# 6x3analogMUX.net
KiCad netlist of a schematic drawn in EAGLE
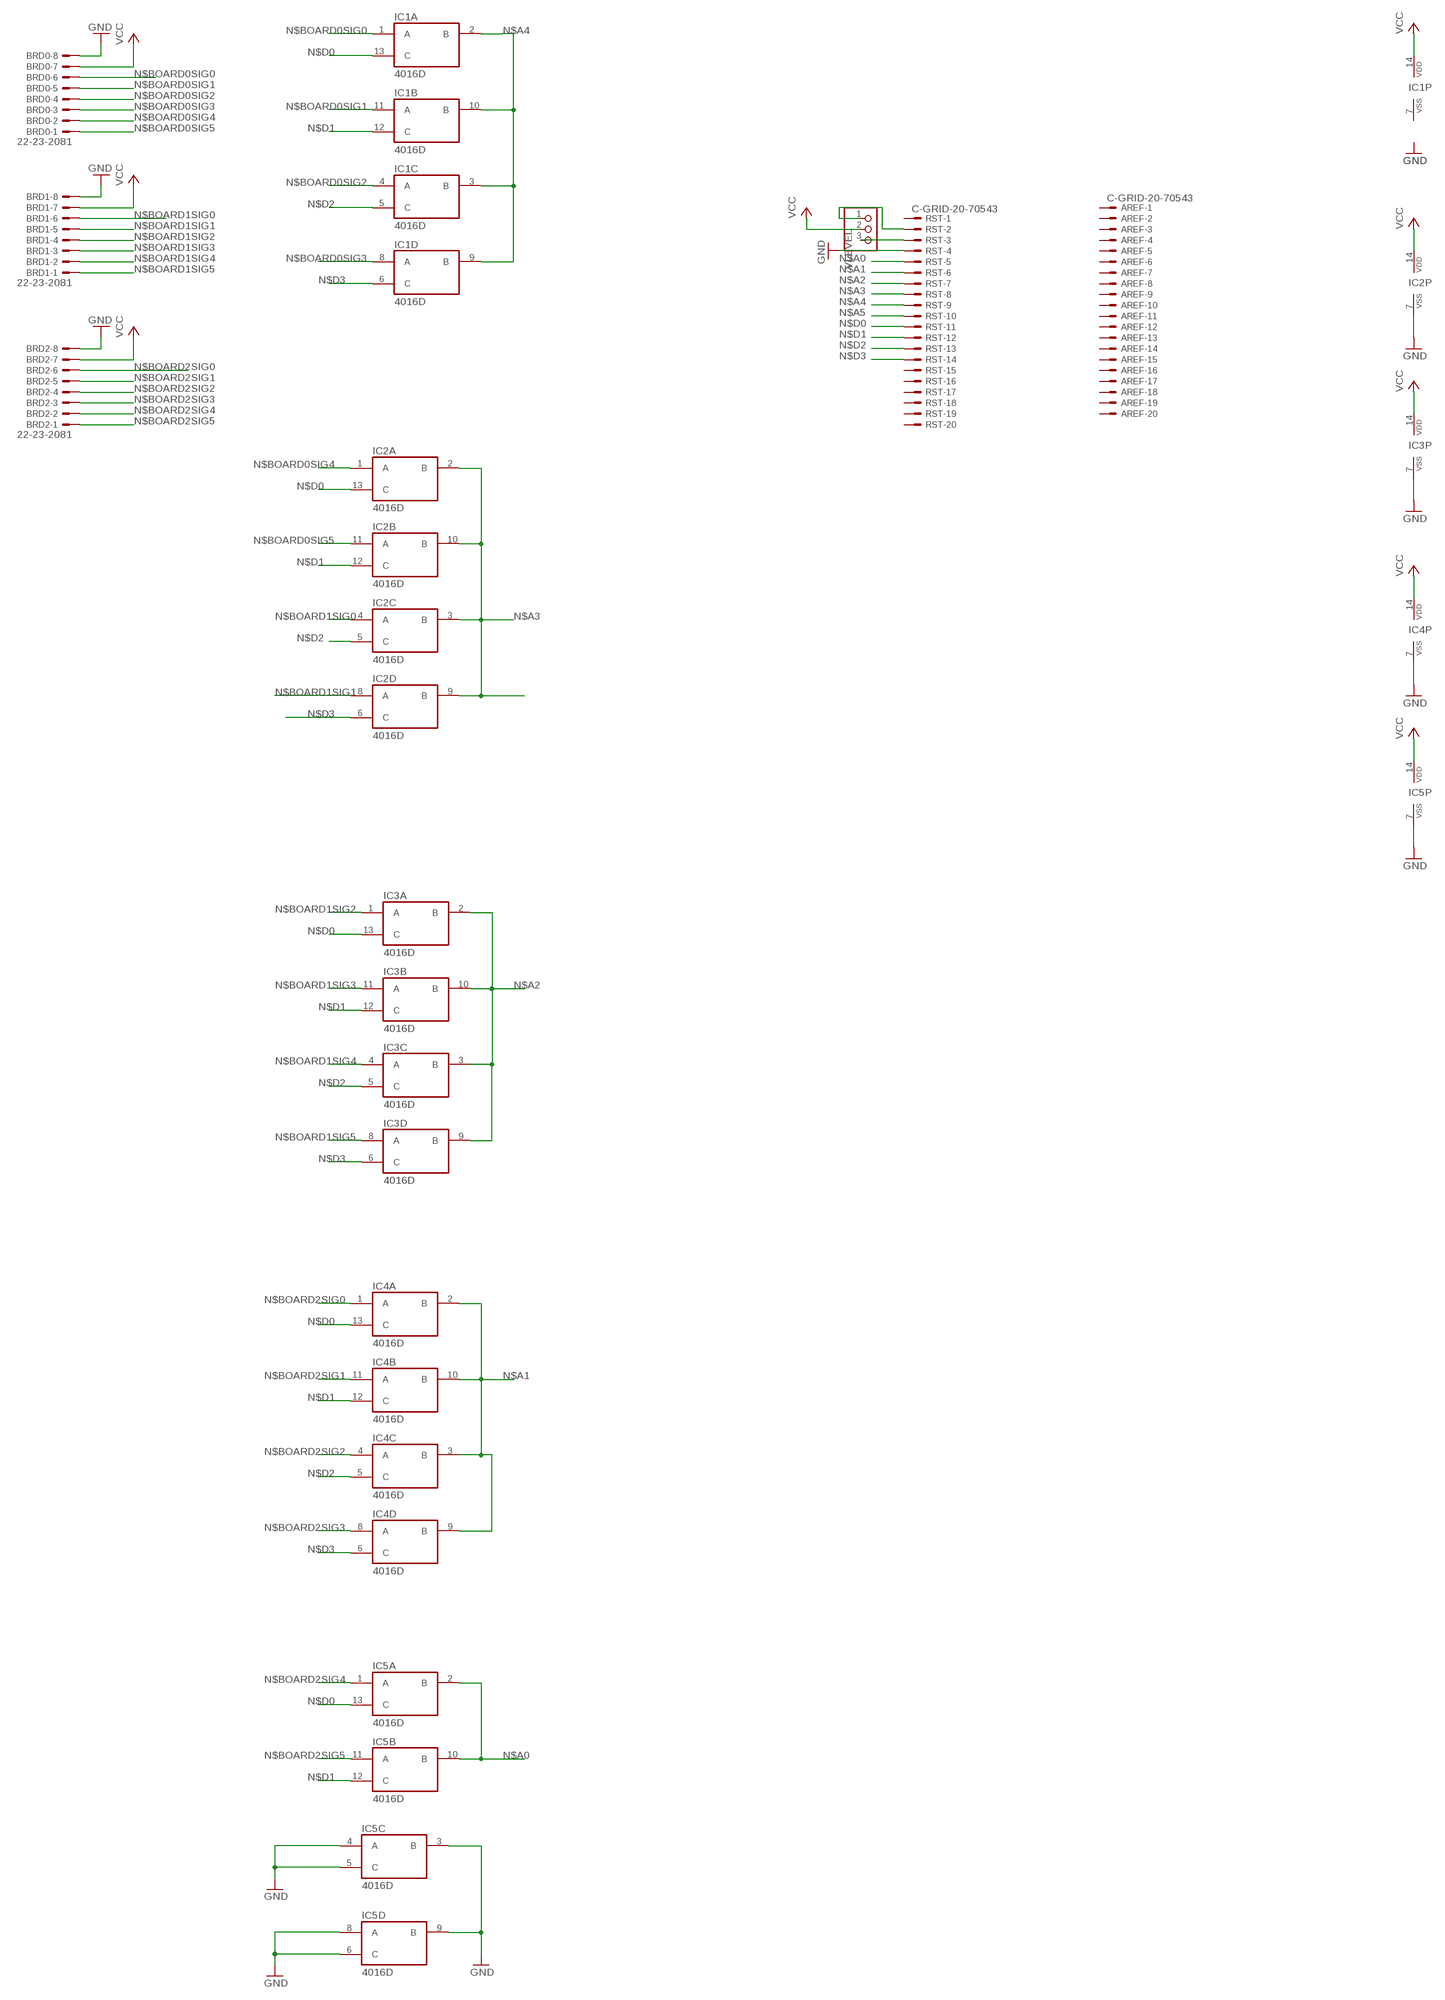
[diagram p0: schematic, sheet 1]

(export (version "E")
  (design (tool "Eeschema 10.0.6"))
  (components
    (comp (ref "AREF")
      (value "C-GRID-20-70543")
      (footprint "eagle-import:70543-20")
      (fields (field (name "MF") "MOLEX"))
      (libsource (lib "eagle-import") (part "C-GRID-20-70543"))
    )
    (comp (ref "BRD0")
      (value "22-23-2081")
      (footprint "eagle-import:22-23-2081")
      (fields (field (name "MF") "MOLEX") (field (name "SPICEPREFIX") "X"))
      (libsource (lib "eagle-import") (part "22-23-2081"))
    )
    (comp (ref "BRD1")
      (value "22-23-2081")
      (footprint "eagle-import:22-23-2081")
      (fields (field (name "MF") "MOLEX"))
      (libsource (lib "eagle-import") (part "22-23-2081"))
    )
    (comp (ref "BRD2")
      (value "22-23-2081")
      (footprint "eagle-import:22-23-2081")
      (fields (field (name "MF") "MOLEX"))
      (libsource (lib "eagle-import") (part "22-23-2081"))
    )
    (comp (ref "IC1")
      (value "4016D")
      (footprint "eagle-import:SO14")
      (libsource (lib "eagle-import") (part "4016D"))
    )
    (comp (ref "IC2")
      (value "4016D")
      (footprint "eagle-import:SO14")
      (libsource (lib "eagle-import") (part "4016D"))
    )
    (comp (ref "IC3")
      (value "4016D")
      (footprint "eagle-import:SO14")
      (libsource (lib "eagle-import") (part "4016D"))
    )
    (comp (ref "IC4")
      (value "4016D")
      (footprint "eagle-import:SO14")
      (libsource (lib "eagle-import") (part "4016D"))
    )
    (comp (ref "IC5")
      (value "4016D")
      (footprint "eagle-import:SO14")
      (libsource (lib "eagle-import") (part "4016D"))
    )
    (comp (ref "RST")
      (value "C-GRID-20-70543")
      (footprint "eagle-import:70543-20")
      (fields (field (name "MF") "MOLEX"))
      (libsource (lib "eagle-import") (part "C-GRID-20-70543"))
    )
    (comp (ref "VLEVEL")
      (value "PINHD-1X3")
      (footprint "eagle-import:1X03")
      (libsource (lib "eagle-import") (part "PINHD-1X3"))
    )
  )
  (nets
    (net (code "1") (name "/N$A0") (class "Default")
      (node (ref "IC5") (pin "10") (pinfunction "B_10") (pintype "tri_state"))
      (node (ref "IC5") (pin "2") (pinfunction "B_2") (pintype "tri_state"))
      (node (ref "RST") (pin "5") (pinfunction "S_5") (pintype "passive"))
    )
    (net (code "2") (name "/N$A1") (class "Default")
      (node (ref "IC4") (pin "10") (pinfunction "B_10") (pintype "tri_state"))
      (node (ref "IC4") (pin "2") (pinfunction "B_2") (pintype "tri_state"))
      (node (ref "IC4") (pin "3") (pinfunction "B_3") (pintype "tri_state"))
      (node (ref "IC4") (pin "9") (pinfunction "B_9") (pintype "tri_state"))
      (node (ref "RST") (pin "6") (pinfunction "S_6") (pintype "passive"))
    )
    (net (code "3") (name "/N$A2") (class "Default")
      (node (ref "IC3") (pin "10") (pinfunction "B_10") (pintype "tri_state"))
      (node (ref "IC3") (pin "2") (pinfunction "B_2") (pintype "tri_state"))
      (node (ref "IC3") (pin "3") (pinfunction "B_3") (pintype "tri_state"))
      (node (ref "IC3") (pin "9") (pinfunction "B_9") (pintype "tri_state"))
      (node (ref "RST") (pin "7") (pinfunction "S_7") (pintype "passive"))
    )
    (net (code "4") (name "/N$A3") (class "Default")
      (node (ref "IC2") (pin "10") (pinfunction "B_10") (pintype "tri_state"))
      (node (ref "IC2") (pin "2") (pinfunction "B_2") (pintype "tri_state"))
      (node (ref "IC2") (pin "3") (pinfunction "B_3") (pintype "tri_state"))
      (node (ref "IC2") (pin "9") (pinfunction "B_9") (pintype "tri_state"))
      (node (ref "RST") (pin "8") (pinfunction "S_8") (pintype "passive"))
    )
    (net (code "5") (name "/N$A4") (class "Default")
      (node (ref "IC1") (pin "10") (pinfunction "B_10") (pintype "tri_state"))
      (node (ref "IC1") (pin "2") (pinfunction "B_2") (pintype "tri_state"))
      (node (ref "IC1") (pin "3") (pinfunction "B_3") (pintype "tri_state"))
      (node (ref "IC1") (pin "9") (pinfunction "B_9") (pintype "tri_state"))
      (node (ref "RST") (pin "9") (pinfunction "S_9") (pintype "passive"))
    )
    (net (code "6") (name "/N$A5") (class "Default")
      (node (ref "RST") (pin "10") (pinfunction "S_10") (pintype "passive"))
    )
    (net (code "7") (name "/N$BOARD0SIG0") (class "Default")
      (node (ref "BRD0") (pin "6") (pinfunction "S_6") (pintype "passive"))
      (node (ref "IC1") (pin "1") (pinfunction "A_1") (pintype "tri_state"))
    )
    (net (code "8") (name "/N$BOARD0SIG1") (class "Default")
      (node (ref "BRD0") (pin "5") (pinfunction "S_5") (pintype "passive"))
      (node (ref "IC1") (pin "11") (pinfunction "A_11") (pintype "tri_state"))
    )
    (net (code "9") (name "/N$BOARD0SIG2") (class "Default")
      (node (ref "BRD0") (pin "4") (pinfunction "S_4") (pintype "passive"))
      (node (ref "IC1") (pin "4") (pinfunction "A_4") (pintype "tri_state"))
    )
    (net (code "10") (name "/N$BOARD0SIG3") (class "Default")
      (node (ref "BRD0") (pin "3") (pinfunction "S_3") (pintype "passive"))
      (node (ref "IC1") (pin "8") (pinfunction "A_8") (pintype "tri_state"))
    )
    (net (code "11") (name "/N$BOARD0SIG4") (class "Default")
      (node (ref "BRD0") (pin "2") (pinfunction "S_2") (pintype "passive"))
      (node (ref "IC2") (pin "1") (pinfunction "A_1") (pintype "tri_state"))
    )
    (net (code "12") (name "/N$BOARD0SIG5") (class "Default")
      (node (ref "BRD0") (pin "1") (pinfunction "S_1") (pintype "passive"))
      (node (ref "IC2") (pin "11") (pinfunction "A_11") (pintype "tri_state"))
    )
    (net (code "13") (name "/N$BOARD1SIG0") (class "Default")
      (node (ref "BRD1") (pin "6") (pinfunction "S_6") (pintype "passive"))
      (node (ref "IC2") (pin "4") (pinfunction "A_4") (pintype "tri_state"))
    )
    (net (code "14") (name "/N$BOARD1SIG1") (class "Default")
      (node (ref "BRD1") (pin "5") (pinfunction "S_5") (pintype "passive"))
      (node (ref "IC2") (pin "8") (pinfunction "A_8") (pintype "tri_state"))
    )
    (net (code "15") (name "/N$BOARD1SIG2") (class "Default")
      (node (ref "BRD1") (pin "4") (pinfunction "S_4") (pintype "passive"))
      (node (ref "IC3") (pin "1") (pinfunction "A_1") (pintype "tri_state"))
    )
    (net (code "16") (name "/N$BOARD1SIG3") (class "Default")
      (node (ref "BRD1") (pin "3") (pinfunction "S_3") (pintype "passive"))
      (node (ref "IC3") (pin "11") (pinfunction "A_11") (pintype "tri_state"))
    )
    (net (code "17") (name "/N$BOARD1SIG4") (class "Default")
      (node (ref "BRD1") (pin "2") (pinfunction "S_2") (pintype "passive"))
      (node (ref "IC3") (pin "4") (pinfunction "A_4") (pintype "tri_state"))
    )
    (net (code "18") (name "/N$BOARD1SIG5") (class "Default")
      (node (ref "BRD1") (pin "1") (pinfunction "S_1") (pintype "passive"))
      (node (ref "IC3") (pin "8") (pinfunction "A_8") (pintype "tri_state"))
    )
    (net (code "19") (name "/N$BOARD2SIG0") (class "Default")
      (node (ref "BRD2") (pin "6") (pinfunction "S_6") (pintype "passive"))
      (node (ref "IC4") (pin "1") (pinfunction "A_1") (pintype "tri_state"))
    )
    (net (code "20") (name "/N$BOARD2SIG1") (class "Default")
      (node (ref "BRD2") (pin "5") (pinfunction "S_5") (pintype "passive"))
      (node (ref "IC4") (pin "11") (pinfunction "A_11") (pintype "tri_state"))
    )
    (net (code "21") (name "/N$BOARD2SIG2") (class "Default")
      (node (ref "BRD2") (pin "4") (pinfunction "S_4") (pintype "passive"))
      (node (ref "IC4") (pin "4") (pinfunction "A_4") (pintype "tri_state"))
    )
    (net (code "22") (name "/N$BOARD2SIG3") (class "Default")
      (node (ref "BRD2") (pin "3") (pinfunction "S_3") (pintype "passive"))
      (node (ref "IC4") (pin "8") (pinfunction "A_8") (pintype "tri_state"))
    )
    (net (code "23") (name "/N$BOARD2SIG4") (class "Default")
      (node (ref "BRD2") (pin "2") (pinfunction "S_2") (pintype "passive"))
      (node (ref "IC5") (pin "1") (pinfunction "A_1") (pintype "tri_state"))
    )
    (net (code "24") (name "/N$BOARD2SIG5") (class "Default")
      (node (ref "BRD2") (pin "1") (pinfunction "S_1") (pintype "passive"))
      (node (ref "IC5") (pin "11") (pinfunction "A_11") (pintype "tri_state"))
    )
    (net (code "25") (name "/N$D0") (class "Default")
      (node (ref "IC1") (pin "13") (pinfunction "C_13") (pintype "input"))
      (node (ref "IC2") (pin "13") (pinfunction "C_13") (pintype "input"))
      (node (ref "IC3") (pin "13") (pinfunction "C_13") (pintype "input"))
      (node (ref "IC4") (pin "13") (pinfunction "C_13") (pintype "input"))
      (node (ref "IC5") (pin "13") (pinfunction "C_13") (pintype "input"))
      (node (ref "RST") (pin "11") (pinfunction "S_11") (pintype "passive"))
    )
    (net (code "26") (name "/N$D1") (class "Default")
      (node (ref "IC1") (pin "12") (pinfunction "C_12") (pintype "input"))
      (node (ref "IC2") (pin "12") (pinfunction "C_12") (pintype "input"))
      (node (ref "IC3") (pin "12") (pinfunction "C_12") (pintype "input"))
      (node (ref "IC4") (pin "12") (pinfunction "C_12") (pintype "input"))
      (node (ref "IC5") (pin "12") (pinfunction "C_12") (pintype "input"))
      (node (ref "RST") (pin "12") (pinfunction "S_12") (pintype "passive"))
    )
    (net (code "27") (name "/N$D2") (class "Default")
      (node (ref "IC1") (pin "5") (pinfunction "C_5") (pintype "input"))
      (node (ref "IC2") (pin "5") (pinfunction "C_5") (pintype "input"))
      (node (ref "IC3") (pin "5") (pinfunction "C_5") (pintype "input"))
      (node (ref "IC4") (pin "5") (pinfunction "C_5") (pintype "input"))
      (node (ref "RST") (pin "13") (pinfunction "S_13") (pintype "passive"))
    )
    (net (code "28") (name "/N$D3") (class "Default")
      (node (ref "IC1") (pin "6") (pinfunction "C_6") (pintype "input"))
      (node (ref "IC2") (pin "6") (pinfunction "C_6") (pintype "input"))
      (node (ref "IC3") (pin "6") (pinfunction "C_6") (pintype "input"))
      (node (ref "IC4") (pin "6") (pinfunction "C_6") (pintype "input"))
      (node (ref "RST") (pin "14") (pinfunction "S_14") (pintype "passive"))
    )
    (net (code "29") (name "/VSS") (class "Default")
      (node (ref "IC1") (pin "7") (pinfunction "VSS_7") (pintype "power_in"))
    )
    (net (code "30") (name "GND") (class "Default")
      (node (ref "BRD0") (pin "8") (pinfunction "S_8") (pintype "passive"))
      (node (ref "BRD1") (pin "8") (pinfunction "S_8") (pintype "passive"))
      (node (ref "BRD2") (pin "8") (pinfunction "S_8") (pintype "passive"))
      (node (ref "IC2") (pin "7") (pinfunction "VSS_7") (pintype "power_in"))
      (node (ref "IC3") (pin "7") (pinfunction "VSS_7") (pintype "power_in"))
      (node (ref "IC4") (pin "7") (pinfunction "VSS_7") (pintype "power_in"))
      (node (ref "IC5") (pin "3") (pinfunction "B_3") (pintype "tri_state"))
      (node (ref "IC5") (pin "4") (pinfunction "A_4") (pintype "tri_state"))
      (node (ref "IC5") (pin "5") (pinfunction "C_5") (pintype "input"))
      (node (ref "IC5") (pin "6") (pinfunction "C_6") (pintype "input"))
      (node (ref "IC5") (pin "7") (pinfunction "VSS_7") (pintype "power_in"))
      (node (ref "IC5") (pin "8") (pinfunction "A_8") (pintype "tri_state"))
      (node (ref "IC5") (pin "9") (pinfunction "B_9") (pintype "tri_state"))
      (node (ref "RST") (pin "4") (pinfunction "S_4") (pintype "passive"))
    )
    (net (code "31") (name "Net-(RSTL-S)") (class "Default")
      (node (ref "RST") (pin "2") (pinfunction "S_2") (pintype "passive"))
      (node (ref "VLEVEL") (pin "1") (pinfunction "1_1") (pintype "passive"))
    )
    (net (code "32") (name "Net-(RSTN-S)") (class "Default")
      (node (ref "RST") (pin "3") (pinfunction "S_3") (pintype "passive"))
      (node (ref "VLEVEL") (pin "3") (pinfunction "3_3") (pintype "passive"))
    )
    (net (code "33") (name "VCC") (class "Default")
      (node (ref "BRD0") (pin "7") (pinfunction "S_7") (pintype "passive"))
      (node (ref "BRD1") (pin "7") (pinfunction "S_7") (pintype "passive"))
      (node (ref "BRD2") (pin "7") (pinfunction "S_7") (pintype "passive"))
      (node (ref "IC1") (pin "14") (pinfunction "VDD_14") (pintype "power_in"))
      (node (ref "IC2") (pin "14") (pinfunction "VDD_14") (pintype "power_in"))
      (node (ref "IC3") (pin "14") (pinfunction "VDD_14") (pintype "power_in"))
      (node (ref "IC4") (pin "14") (pinfunction "VDD_14") (pintype "power_in"))
      (node (ref "IC5") (pin "14") (pinfunction "VDD_14") (pintype "power_in"))
      (node (ref "VLEVEL") (pin "2") (pinfunction "2_2") (pintype "passive"))
    )
    (net (code "34") (name "unconnected-(AREFA-S-Pad1)") (class "Default")
      (node (ref "AREF") (pin "1") (pinfunction "S_1") (pintype "passive"))
    )
    (net (code "35") (name "unconnected-(AREFB-S-Pad10)") (class "Default")
      (node (ref "AREF") (pin "10") (pinfunction "S_10") (pintype "passive"))
    )
    (net (code "36") (name "unconnected-(AREFC-S-Pad11)") (class "Default")
      (node (ref "AREF") (pin "11") (pinfunction "S_11") (pintype "passive"))
    )
    (net (code "37") (name "unconnected-(AREFD-S-Pad12)") (class "Default")
      (node (ref "AREF") (pin "12") (pinfunction "S_12") (pintype "passive"))
    )
    (net (code "38") (name "unconnected-(AREFE-S-Pad13)") (class "Default")
      (node (ref "AREF") (pin "13") (pinfunction "S_13") (pintype "passive"))
    )
    (net (code "39") (name "unconnected-(AREFF-S-Pad14)") (class "Default")
      (node (ref "AREF") (pin "14") (pinfunction "S_14") (pintype "passive"))
    )
    (net (code "40") (name "unconnected-(AREFG-S-Pad15)") (class "Default")
      (node (ref "AREF") (pin "15") (pinfunction "S_15") (pintype "passive"))
    )
    (net (code "41") (name "unconnected-(AREFH-S-Pad16)") (class "Default")
      (node (ref "AREF") (pin "16") (pinfunction "S_16") (pintype "passive"))
    )
    (net (code "42") (name "unconnected-(AREFI-S-Pad17)") (class "Default")
      (node (ref "AREF") (pin "17") (pinfunction "S_17") (pintype "passive"))
    )
    (net (code "43") (name "unconnected-(AREFJ-S-Pad18)") (class "Default")
      (node (ref "AREF") (pin "18") (pinfunction "S_18") (pintype "passive"))
    )
    (net (code "44") (name "unconnected-(AREFK-S-Pad19)") (class "Default")
      (node (ref "AREF") (pin "19") (pinfunction "S_19") (pintype "passive"))
    )
    (net (code "45") (name "unconnected-(AREFL-S-Pad2)") (class "Default")
      (node (ref "AREF") (pin "2") (pinfunction "S_2") (pintype "passive"))
    )
    (net (code "46") (name "unconnected-(AREFM-S-Pad20)") (class "Default")
      (node (ref "AREF") (pin "20") (pinfunction "S_20") (pintype "passive"))
    )
    (net (code "47") (name "unconnected-(AREFN-S-Pad3)") (class "Default")
      (node (ref "AREF") (pin "3") (pinfunction "S_3") (pintype "passive"))
    )
    (net (code "48") (name "unconnected-(AREFO-S-Pad4)") (class "Default")
      (node (ref "AREF") (pin "4") (pinfunction "S_4") (pintype "passive"))
    )
    (net (code "49") (name "unconnected-(AREFP-S-Pad5)") (class "Default")
      (node (ref "AREF") (pin "5") (pinfunction "S_5") (pintype "passive"))
    )
    (net (code "50") (name "unconnected-(AREFQ-S-Pad6)") (class "Default")
      (node (ref "AREF") (pin "6") (pinfunction "S_6") (pintype "passive"))
    )
    (net (code "51") (name "unconnected-(AREFR-S-Pad7)") (class "Default")
      (node (ref "AREF") (pin "7") (pinfunction "S_7") (pintype "passive"))
    )
    (net (code "52") (name "unconnected-(AREFS-S-Pad8)") (class "Default")
      (node (ref "AREF") (pin "8") (pinfunction "S_8") (pintype "passive"))
    )
    (net (code "53") (name "unconnected-(AREFT-S-Pad9)") (class "Default")
      (node (ref "AREF") (pin "9") (pinfunction "S_9") (pintype "passive"))
    )
    (net (code "54") (name "unconnected-(RSTA-S-Pad1)") (class "Default")
      (node (ref "RST") (pin "1") (pinfunction "S_1") (pintype "passive"))
    )
    (net (code "55") (name "unconnected-(RSTG-S-Pad15)") (class "Default")
      (node (ref "RST") (pin "15") (pinfunction "S_15") (pintype "passive"))
    )
    (net (code "56") (name "unconnected-(RSTH-S-Pad16)") (class "Default")
      (node (ref "RST") (pin "16") (pinfunction "S_16") (pintype "passive"))
    )
    (net (code "57") (name "unconnected-(RSTI-S-Pad17)") (class "Default")
      (node (ref "RST") (pin "17") (pinfunction "S_17") (pintype "passive"))
    )
    (net (code "58") (name "unconnected-(RSTJ-S-Pad18)") (class "Default")
      (node (ref "RST") (pin "18") (pinfunction "S_18") (pintype "passive"))
    )
    (net (code "59") (name "unconnected-(RSTK-S-Pad19)") (class "Default")
      (node (ref "RST") (pin "19") (pinfunction "S_19") (pintype "passive"))
    )
    (net (code "60") (name "unconnected-(RSTM-S-Pad20)") (class "Default")
      (node (ref "RST") (pin "20") (pinfunction "S_20") (pintype "passive"))
    )
  )
)
